# SparkFun_Buck_Regulator_Breakout_-_AP632.net
KiCad netlist of a schematic drawn in EAGLE
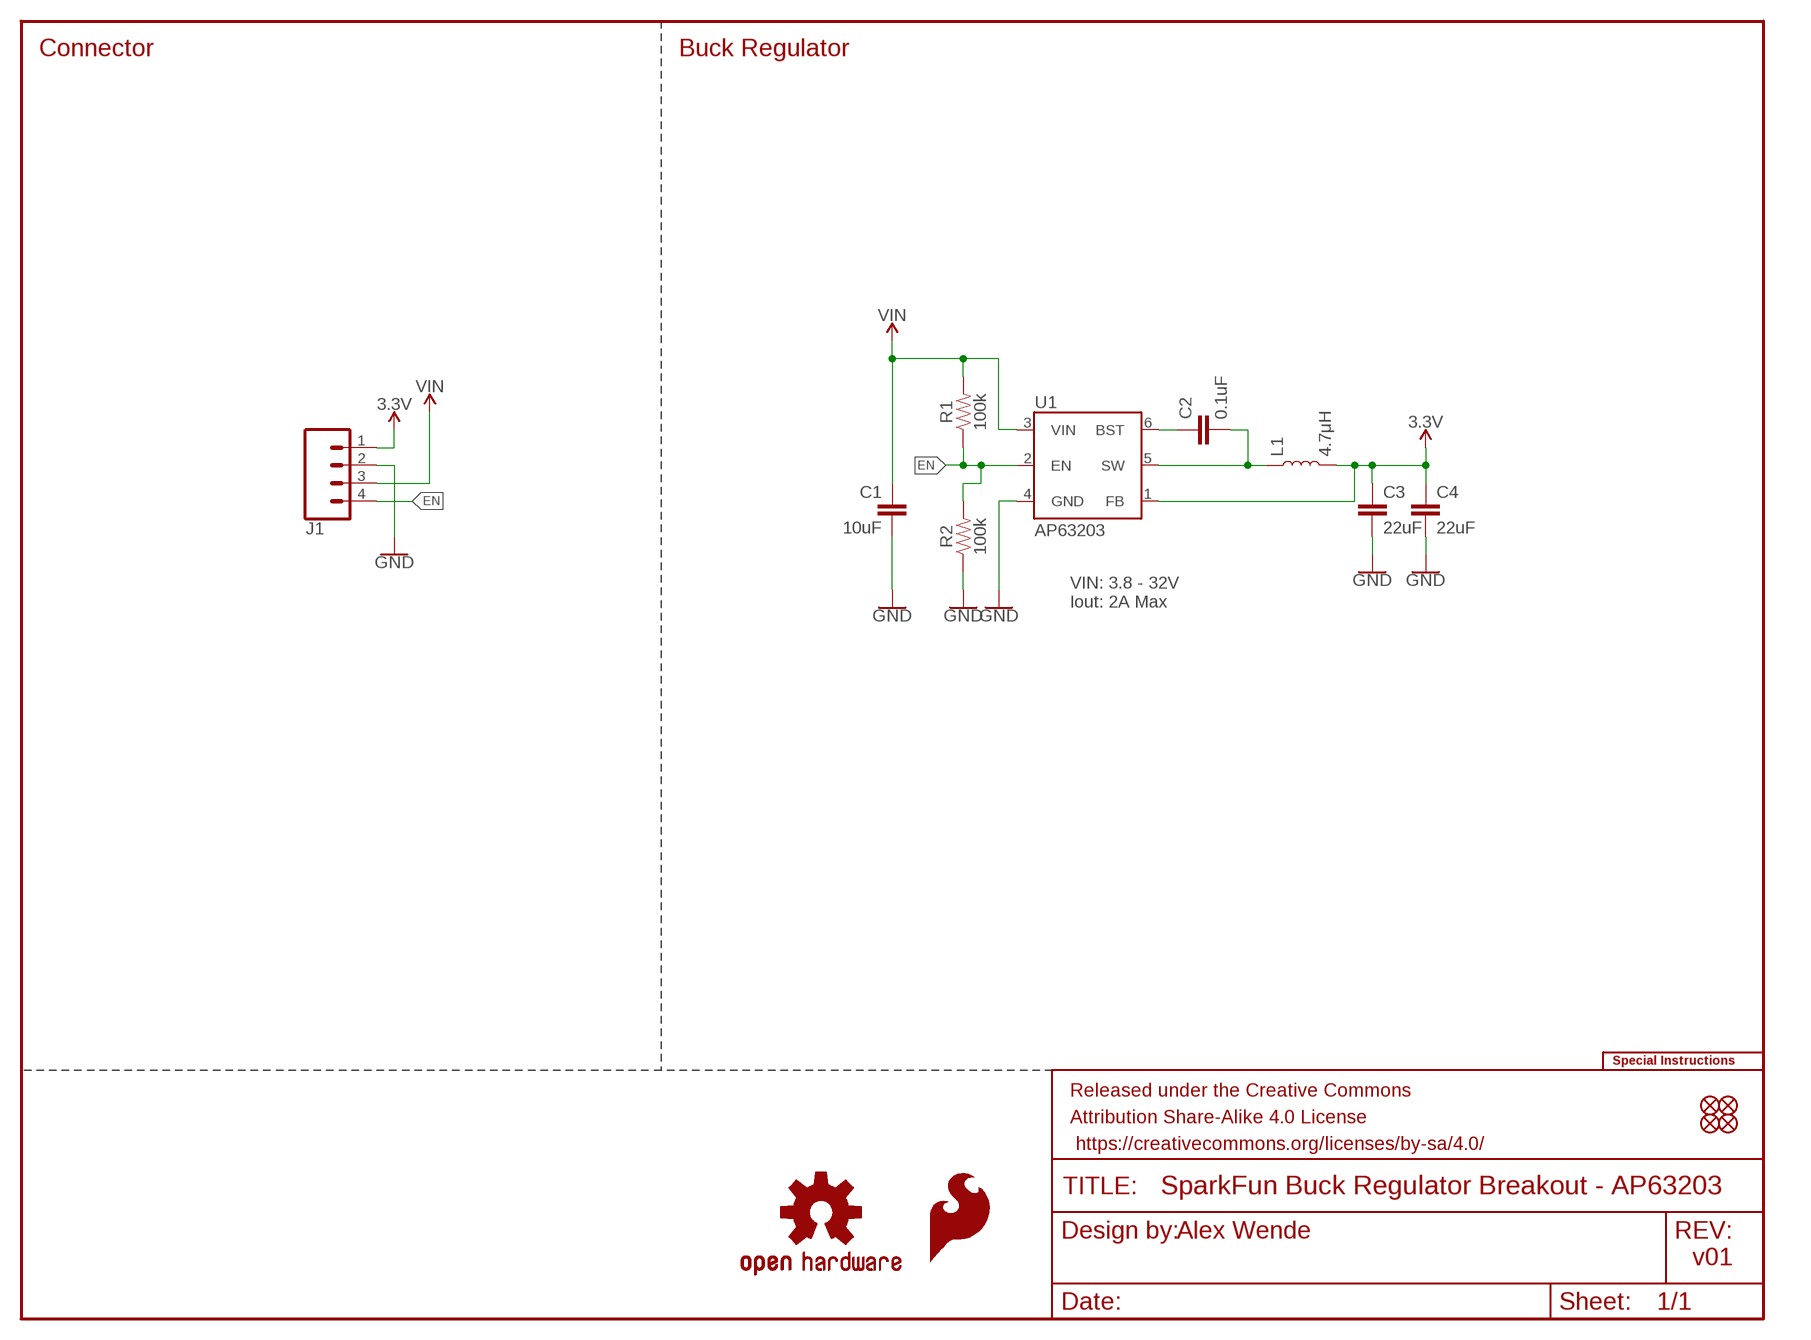
[diagram p0: schematic, sheet 1]

(export (version "E")
  (design (tool "Eeschema 10.0.6"))
  (components
    (comp (ref "C1")
      (value "10uF")
      (footprint "eagle-import:1210")
      (libsource (lib "eagle-import") (part "10UF-1210-50V-20%"))
    )
    (comp (ref "C2")
      (value "0.1uF")
      (footprint "eagle-import:0603")
      (libsource (lib "eagle-import") (part "0.1UF-0603-25V-5%"))
    )
    (comp (ref "C3")
      (value "22uF")
      (footprint "eagle-import:0603")
      (libsource (lib "eagle-import") (part "22UF-0603-6.3V-20%"))
    )
    (comp (ref "C4")
      (value "22uF")
      (footprint "eagle-import:0603")
      (libsource (lib "eagle-import") (part "22UF-0603-6.3V-20%"))
    )
    (comp (ref "FD1")
      (value "FIDUCIAL0.2MM")
      (footprint "eagle-import:FIDUCIAL-0.2MM")
      (libsource (lib "eagle-import") (part "FIDUCIAL0.2MM"))
    )
    (comp (ref "FD2")
      (value "FIDUCIAL0.2MM")
      (footprint "eagle-import:FIDUCIAL-0.2MM")
      (libsource (lib "eagle-import") (part "FIDUCIAL0.2MM"))
    )
    (comp (ref "FD3")
      (value "FIDUCIAL0.2MM")
      (footprint "eagle-import:FIDUCIAL-0.2MM")
      (libsource (lib "eagle-import") (part "FIDUCIAL0.2MM"))
    )
    (comp (ref "FD4")
      (value "FIDUCIAL0.2MM")
      (footprint "eagle-import:FIDUCIAL-0.2MM")
      (libsource (lib "eagle-import") (part "FIDUCIAL0.2MM"))
    )
    (comp (ref "FRAME1")
      (value "FRAME-LETTER")
      (footprint "eagle-import:CREATIVE_COMMONS")
      (libsource (lib "eagle-import") (part "FRAME-LETTER"))
    )
    (comp (ref "J1")
      (value "CONN_041X04_NO_SILK")
      (footprint "eagle-import:1X04_NO_SILK")
      (libsource (lib "eagle-import") (part "CONN_041X04_NO_SILK"))
    )
    (comp (ref "L1")
      (value "4.7μH")
      (footprint "eagle-import:INDUCTOR_4X4MM")
      (libsource (lib "eagle-import") (part "4.7μH_SHIELDED_INDUCTORNPIS_LS"))
    )
    (comp (ref "LOGO1")
      (value "SFE_LOGO_FLAME.1_INCH")
      (footprint "eagle-import:SFE_LOGO_FLAME_.1")
      (libsource (lib "eagle-import") (part "SFE_LOGO_FLAME.1_INCH"))
    )
    (comp (ref "LOGO2")
      (value "OSHW-LOGOS")
      (footprint "eagle-import:OSHW-LOGO-S")
      (libsource (lib "eagle-import") (part "OSHW-LOGOS"))
    )
    (comp (ref "LOGO3")
      (value "SPECIAL_INSTRUCTIONS-ORDERING")
      (footprint "eagle-import:ORDERING_INSTRUCTIONS")
      (libsource (lib "eagle-import") (part "SPECIAL_INSTRUCTIONS-ORDERING"))
    )
    (comp (ref "R1")
      (value "100k")
      (footprint "eagle-import:0603")
      (libsource (lib "eagle-import") (part "100KOHM-0603-1/10W-1%"))
    )
    (comp (ref "R2")
      (value "100k")
      (footprint "eagle-import:0603")
      (libsource (lib "eagle-import") (part "100KOHM-0603-1/10W-1%"))
    )
    (comp (ref "U1")
      (value "AP63203")
      (footprint "eagle-import:SOT23-6")
      (libsource (lib "eagle-import") (part "AP63203"))
    )
  )
  (nets
    (net (code "1") (name "3.3V") (class "Default")
      (node (ref "C3") (pin "1") (pinfunction "1_1") (pintype "passive"))
      (node (ref "C4") (pin "1") (pinfunction "1_1") (pintype "passive"))
      (node (ref "J1") (pin "1") (pinfunction "1_1") (pintype "passive"))
      (node (ref "L1") (pin "P$2") (pinfunction "2_P$2") (pintype "passive"))
      (node (ref "U1") (pin "1") (pinfunction "FB_1") (pintype "bidirectional"))
    )
    (net (code "2") (name "EN") (class "Default")
      (node (ref "J1") (pin "4") (pinfunction "4_4") (pintype "passive"))
      (node (ref "R1") (pin "1") (pinfunction "1_1") (pintype "passive"))
      (node (ref "R2") (pin "2") (pinfunction "2_2") (pintype "passive"))
      (node (ref "U1") (pin "2") (pinfunction "EN_2") (pintype "bidirectional"))
    )
    (net (code "3") (name "GND") (class "Default")
      (node (ref "C1") (pin "2") (pinfunction "2_2") (pintype "passive"))
      (node (ref "C3") (pin "2") (pinfunction "2_2") (pintype "passive"))
      (node (ref "C4") (pin "2") (pinfunction "2_2") (pintype "passive"))
      (node (ref "J1") (pin "2") (pinfunction "2_2") (pintype "passive"))
      (node (ref "R2") (pin "1") (pinfunction "1_1") (pintype "passive"))
      (node (ref "U1") (pin "4") (pinfunction "GND_4") (pintype "bidirectional"))
    )
    (net (code "4") (name "Net-(L1-1)") (class "Default")
      (node (ref "C2") (pin "2") (pinfunction "2_2") (pintype "passive"))
      (node (ref "L1") (pin "P$1") (pinfunction "1_P$1") (pintype "passive"))
      (node (ref "U1") (pin "5") (pinfunction "SW_5") (pintype "bidirectional"))
    )
    (net (code "5") (name "Net-(U1-BST)") (class "Default")
      (node (ref "C2") (pin "1") (pinfunction "1_1") (pintype "passive"))
      (node (ref "U1") (pin "6") (pinfunction "BST_6") (pintype "bidirectional"))
    )
    (net (code "6") (name "VIN") (class "Default")
      (node (ref "C1") (pin "1") (pinfunction "1_1") (pintype "passive"))
      (node (ref "J1") (pin "3") (pinfunction "3_3") (pintype "passive"))
      (node (ref "R1") (pin "2") (pinfunction "2_2") (pintype "passive"))
      (node (ref "U1") (pin "3") (pinfunction "VIN_3") (pintype "bidirectional"))
    )
  )
)
